# display.net
KiCad netlist of a schematic drawn in EAGLE
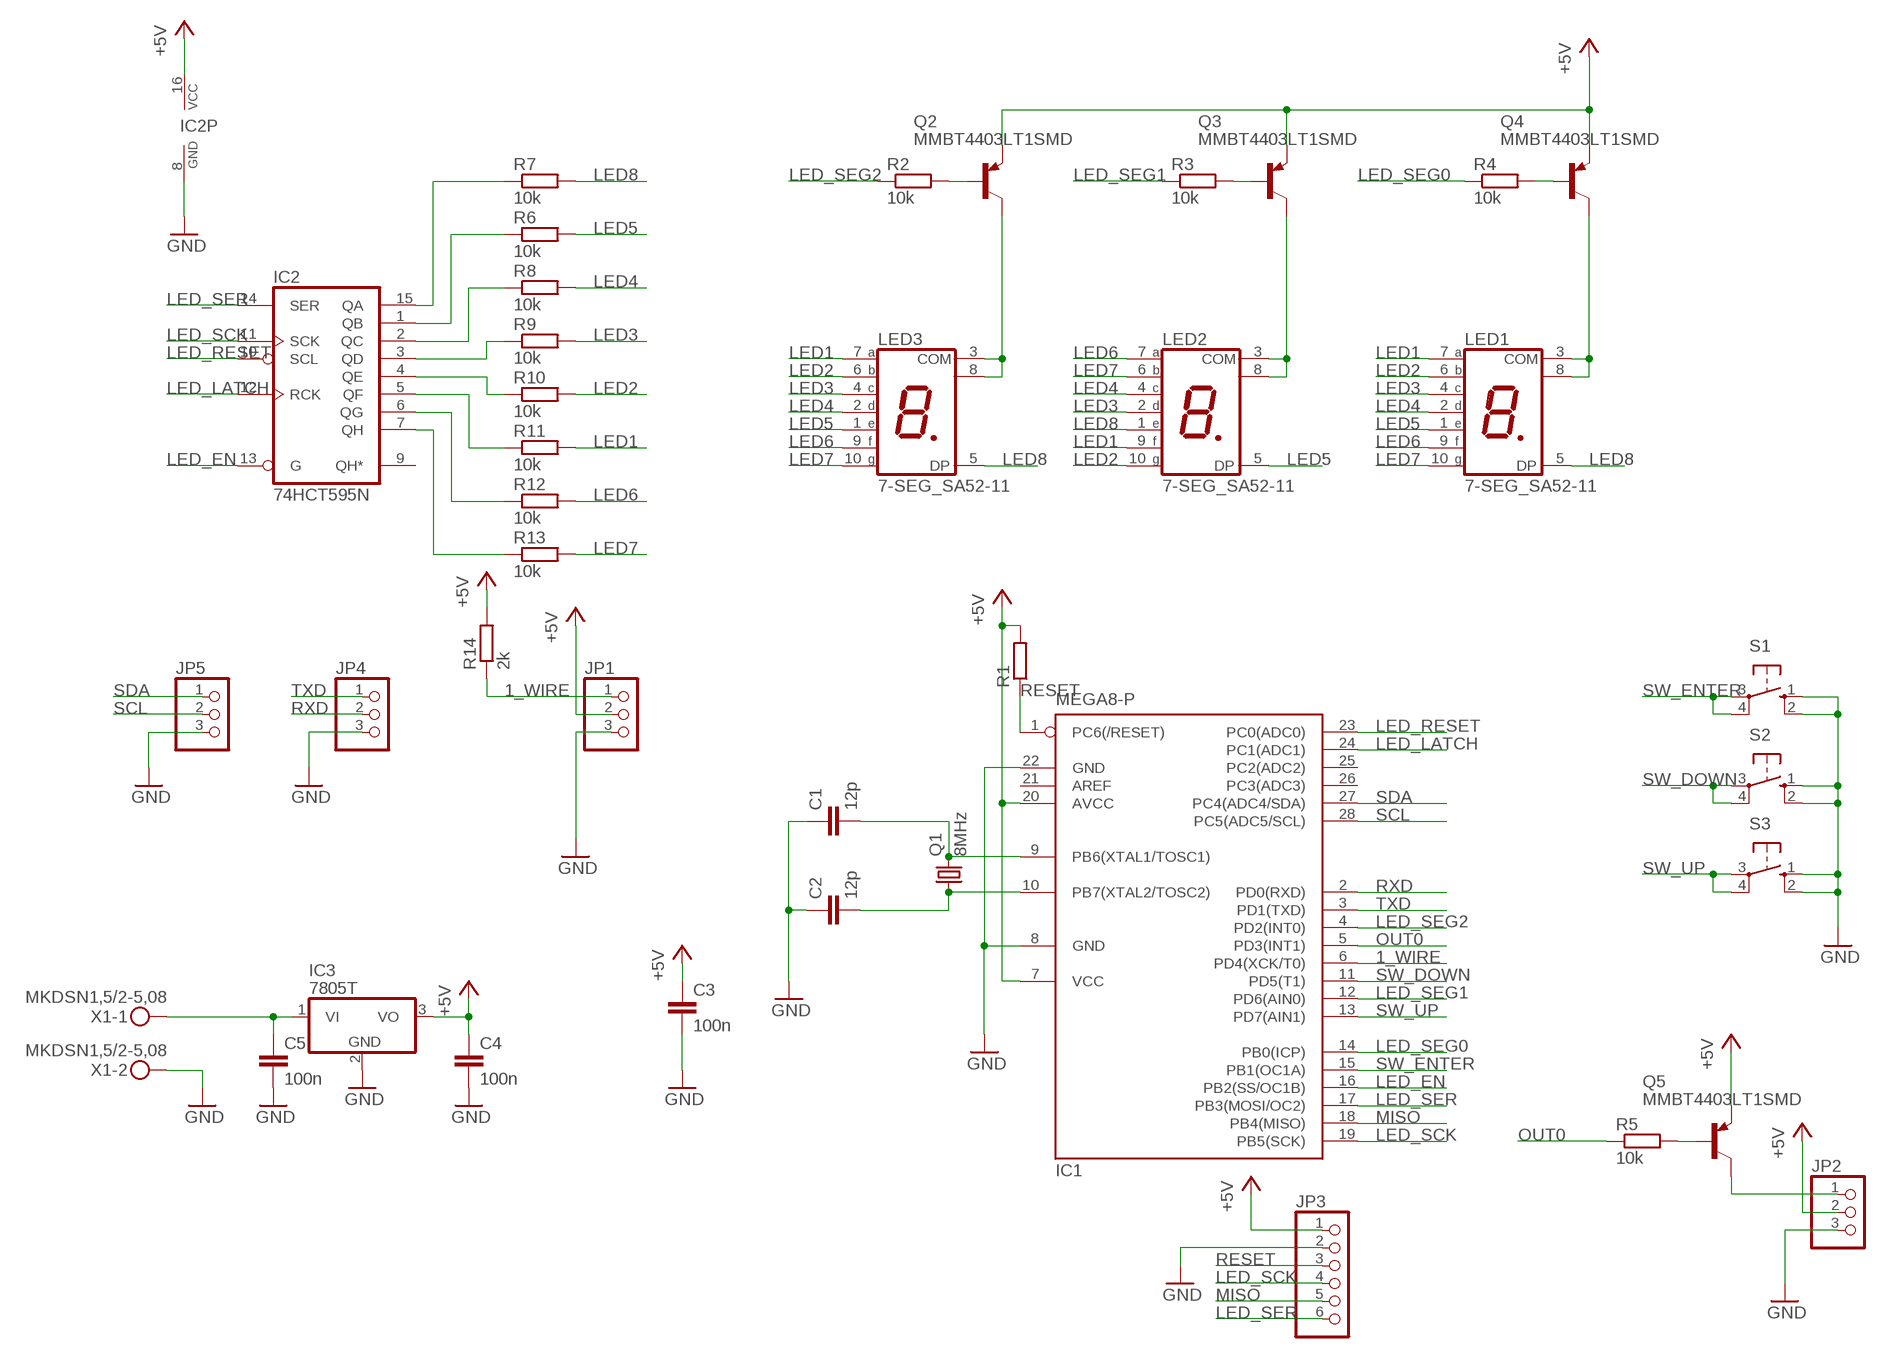
[diagram p0: schematic, sheet 1]

(export (version "E")
  (design (tool "Eeschema 10.0.6"))
  (components
    (comp (ref "C1")
      (value "12p")
      (footprint "eagle-import:C050-035X075")
      (libsource (lib "eagle-import") (part "C-EU050-035X075"))
    )
    (comp (ref "C2")
      (value "12p")
      (footprint "eagle-import:C050-035X075")
      (libsource (lib "eagle-import") (part "C-EU050-035X075"))
    )
    (comp (ref "C3")
      (value "100n")
      (footprint "eagle-import:C050-030X075")
      (libsource (lib "eagle-import") (part "C-EU050-030X075"))
    )
    (comp (ref "C4")
      (value "100n")
      (footprint "eagle-import:C050-030X075")
      (libsource (lib "eagle-import") (part "C-EU050-030X075"))
    )
    (comp (ref "C5")
      (value "100n")
      (footprint "eagle-import:C050-030X075")
      (libsource (lib "eagle-import") (part "C-EU050-030X075"))
    )
    (comp (ref "IC1")
      (value "MEGA8-P")
      (footprint "eagle-import:DIL28-3")
      (libsource (lib "eagle-import") (part "MEGA8-P"))
    )
    (comp (ref "IC2")
      (value "74HCT595N")
      (footprint "eagle-import:DIL16")
      (libsource (lib "eagle-import") (part "74595NHCT"))
    )
    (comp (ref "IC3")
      (value "7805T")
      (footprint "eagle-import:TO220H")
      (libsource (lib "eagle-import") (part "78T05"))
    )
    (comp (ref "JP1")
      (value "PINHD-1X3")
      (footprint "eagle-import:1X03")
      (libsource (lib "eagle-import") (part "PINHD-1X3"))
    )
    (comp (ref "JP2")
      (value "PINHD-1X3")
      (footprint "eagle-import:1X03")
      (libsource (lib "eagle-import") (part "PINHD-1X3"))
    )
    (comp (ref "JP3")
      (value "PINHD-1X6")
      (footprint "eagle-import:1X06")
      (libsource (lib "eagle-import") (part "PINHD-1X6"))
    )
    (comp (ref "JP4")
      (value "PINHD-1X3")
      (footprint "eagle-import:1X03")
      (libsource (lib "eagle-import") (part "PINHD-1X3"))
    )
    (comp (ref "JP5")
      (value "PINHD-1X3")
      (footprint "eagle-import:1X03")
      (libsource (lib "eagle-import") (part "PINHD-1X3"))
    )
    (comp (ref "LED1")
      (value "7-SEG_SA52-11")
      (footprint "eagle-import:SA52-11")
      (libsource (lib "eagle-import") (part "7-SEG_SA52-11"))
    )
    (comp (ref "LED2")
      (value "7-SEG_SA52-11")
      (footprint "eagle-import:SA52-11")
      (libsource (lib "eagle-import") (part "7-SEG_SA52-11"))
    )
    (comp (ref "LED3")
      (value "7-SEG_SA52-11")
      (footprint "eagle-import:SA52-11")
      (libsource (lib "eagle-import") (part "7-SEG_SA52-11"))
    )
    (comp (ref "Q1")
      (value "8MHz")
      (footprint "eagle-import:HC49U70")
      (libsource (lib "eagle-import") (part "CRYSTALHC49U70"))
    )
    (comp (ref "Q2")
      (value "MMBT4403LT1SMD")
      (footprint "eagle-import:SOT23-BEC")
      (libsource (lib "eagle-import") (part "MMBT4403SMDLT1"))
    )
    (comp (ref "Q3")
      (value "MMBT4403LT1SMD")
      (footprint "eagle-import:SOT23-BEC")
      (libsource (lib "eagle-import") (part "MMBT4403SMDLT1"))
    )
    (comp (ref "Q4")
      (value "MMBT4403LT1SMD")
      (footprint "eagle-import:SOT23-BEC")
      (libsource (lib "eagle-import") (part "MMBT4403SMDLT1"))
    )
    (comp (ref "Q5")
      (value "MMBT4403LT1SMD")
      (footprint "eagle-import:SOT23-BEC")
      (libsource (lib "eagle-import") (part "MMBT4403SMDLT1"))
    )
    (comp (ref "R1")
      (value "R-EU_R1206")
      (footprint "eagle-import:R1206")
      (libsource (lib "eagle-import") (part "R-EU_R1206"))
    )
    (comp (ref "R2")
      (value "10k")
      (footprint "eagle-import:M1206")
      (libsource (lib "eagle-import") (part "R-EU_M1206"))
    )
    (comp (ref "R3")
      (value "10k")
      (footprint "eagle-import:M1206")
      (libsource (lib "eagle-import") (part "R-EU_M1206"))
    )
    (comp (ref "R4")
      (value "10k")
      (footprint "eagle-import:M1206")
      (libsource (lib "eagle-import") (part "R-EU_M1206"))
    )
    (comp (ref "R5")
      (value "10k")
      (footprint "eagle-import:M1206")
      (libsource (lib "eagle-import") (part "R-EU_M1206"))
    )
    (comp (ref "R6")
      (value "10k")
      (footprint "eagle-import:M1206")
      (libsource (lib "eagle-import") (part "R-EU_M1206"))
    )
    (comp (ref "R7")
      (value "10k")
      (footprint "eagle-import:M1206")
      (libsource (lib "eagle-import") (part "R-EU_M1206"))
    )
    (comp (ref "R8")
      (value "10k")
      (footprint "eagle-import:M1206")
      (libsource (lib "eagle-import") (part "R-EU_M1206"))
    )
    (comp (ref "R9")
      (value "10k")
      (footprint "eagle-import:M1206")
      (libsource (lib "eagle-import") (part "R-EU_M1206"))
    )
    (comp (ref "R10")
      (value "10k")
      (footprint "eagle-import:M1206")
      (libsource (lib "eagle-import") (part "R-EU_M1206"))
    )
    (comp (ref "R11")
      (value "10k")
      (footprint "eagle-import:M1206")
      (libsource (lib "eagle-import") (part "R-EU_M1206"))
    )
    (comp (ref "R12")
      (value "10k")
      (footprint "eagle-import:M1206")
      (libsource (lib "eagle-import") (part "R-EU_M1206"))
    )
    (comp (ref "R13")
      (value "10k")
      (footprint "eagle-import:M1206")
      (libsource (lib "eagle-import") (part "R-EU_M1206"))
    )
    (comp (ref "R14")
      (value "2k")
      (footprint "eagle-import:M1206")
      (libsource (lib "eagle-import") (part "R-EU_M1206"))
    )
    (comp (ref "S1")
      (value "10-XX")
      (footprint "eagle-import:B3F-10XX")
      (fields (field (name "MPN") "B3F-1000"))
      (libsource (lib "eagle-import") (part "10-XX"))
    )
    (comp (ref "S2")
      (value "10-XX")
      (footprint "eagle-import:B3F-10XX")
      (fields (field (name "MPN") "B3F-1000"))
      (libsource (lib "eagle-import") (part "10-XX"))
    )
    (comp (ref "S3")
      (value "10-XX")
      (footprint "eagle-import:B3F-10XX")
      (fields (field (name "MPN") "B3F-1000"))
      (libsource (lib "eagle-import") (part "10-XX"))
    )
    (comp (ref "X1")
      (value "MKDSN1,5/2-5,08")
      (footprint "eagle-import:MKDSN1,5_2-5,08")
      (fields (field (name "MPN") "MKDSN 1,5/2-5.08"))
      (libsource (lib "eagle-import") (part "MKDSN1,5/2-5,08"))
    )
  )
  (nets
    (net (code "1") (name "+5V") (class "Default")
      (node (ref "C3") (pin "1") (pinfunction "1_1") (pintype "passive"))
      (node (ref "C4") (pin "1") (pinfunction "1_1") (pintype "passive"))
      (node (ref "IC1") (pin "20") (pinfunction "AVCC_20") (pintype "power_in"))
      (node (ref "IC1") (pin "7") (pinfunction "VCC_7") (pintype "power_in"))
      (node (ref "IC2") (pin "16") (pinfunction "VCC_16") (pintype "power_in"))
      (node (ref "IC3") (pin "3") (pinfunction "VO_3") (pintype "passive"))
      (node (ref "JP1") (pin "2") (pinfunction "2_2") (pintype "passive"))
      (node (ref "JP2") (pin "2") (pinfunction "2_2") (pintype "passive"))
      (node (ref "JP3") (pin "1") (pinfunction "1_1") (pintype "passive"))
      (node (ref "Q2") (pin "E") (pinfunction "E_E") (pintype "passive"))
      (node (ref "Q3") (pin "E") (pinfunction "E_E") (pintype "passive"))
      (node (ref "Q4") (pin "E") (pinfunction "E_E") (pintype "passive"))
      (node (ref "Q5") (pin "E") (pinfunction "E_E") (pintype "passive"))
      (node (ref "R1") (pin "2") (pinfunction "2_2") (pintype "passive"))
      (node (ref "R14") (pin "2") (pinfunction "2_2") (pintype "passive"))
    )
    (net (code "2") (name "/1_WIRE") (class "Default")
      (node (ref "IC1") (pin "6") (pinfunction "PD4(XCK/T0)_6") (pintype "bidirectional"))
      (node (ref "JP1") (pin "1") (pinfunction "1_1") (pintype "passive"))
      (node (ref "R14") (pin "1") (pinfunction "1_1") (pintype "passive"))
    )
    (net (code "3") (name "/LED1") (class "Default")
      (node (ref "LED1") (pin "7") (pinfunction "A_7") (pintype "passive"))
      (node (ref "LED2") (pin "9") (pinfunction "F_9") (pintype "passive"))
      (node (ref "LED3") (pin "7") (pinfunction "A_7") (pintype "passive"))
      (node (ref "R11") (pin "2") (pinfunction "2_2") (pintype "passive"))
    )
    (net (code "4") (name "/LED2") (class "Default")
      (node (ref "LED1") (pin "6") (pinfunction "B_6") (pintype "passive"))
      (node (ref "LED2") (pin "10") (pinfunction "G_10") (pintype "passive"))
      (node (ref "LED3") (pin "6") (pinfunction "B_6") (pintype "passive"))
      (node (ref "R10") (pin "2") (pinfunction "2_2") (pintype "passive"))
    )
    (net (code "5") (name "/LED3") (class "Default")
      (node (ref "LED1") (pin "4") (pinfunction "C_4") (pintype "passive"))
      (node (ref "LED2") (pin "2") (pinfunction "D_2") (pintype "passive"))
      (node (ref "LED3") (pin "4") (pinfunction "C_4") (pintype "passive"))
      (node (ref "R9") (pin "2") (pinfunction "2_2") (pintype "passive"))
    )
    (net (code "6") (name "/LED4") (class "Default")
      (node (ref "LED1") (pin "2") (pinfunction "D_2") (pintype "passive"))
      (node (ref "LED2") (pin "4") (pinfunction "C_4") (pintype "passive"))
      (node (ref "LED3") (pin "2") (pinfunction "D_2") (pintype "passive"))
      (node (ref "R8") (pin "2") (pinfunction "2_2") (pintype "passive"))
    )
    (net (code "7") (name "/LED5") (class "Default")
      (node (ref "LED1") (pin "1") (pinfunction "E_1") (pintype "passive"))
      (node (ref "LED2") (pin "5") (pinfunction "DP_5") (pintype "passive"))
      (node (ref "LED3") (pin "1") (pinfunction "E_1") (pintype "passive"))
      (node (ref "R6") (pin "2") (pinfunction "2_2") (pintype "passive"))
    )
    (net (code "8") (name "/LED6") (class "Default")
      (node (ref "LED1") (pin "9") (pinfunction "F_9") (pintype "passive"))
      (node (ref "LED2") (pin "7") (pinfunction "A_7") (pintype "passive"))
      (node (ref "LED3") (pin "9") (pinfunction "F_9") (pintype "passive"))
      (node (ref "R12") (pin "2") (pinfunction "2_2") (pintype "passive"))
    )
    (net (code "9") (name "/LED7") (class "Default")
      (node (ref "LED1") (pin "10") (pinfunction "G_10") (pintype "passive"))
      (node (ref "LED2") (pin "6") (pinfunction "B_6") (pintype "passive"))
      (node (ref "LED3") (pin "10") (pinfunction "G_10") (pintype "passive"))
      (node (ref "R13") (pin "2") (pinfunction "2_2") (pintype "passive"))
    )
    (net (code "10") (name "/LED8") (class "Default")
      (node (ref "LED1") (pin "5") (pinfunction "DP_5") (pintype "passive"))
      (node (ref "LED2") (pin "1") (pinfunction "E_1") (pintype "passive"))
      (node (ref "LED3") (pin "5") (pinfunction "DP_5") (pintype "passive"))
      (node (ref "R7") (pin "2") (pinfunction "2_2") (pintype "passive"))
    )
    (net (code "11") (name "/LED_EN") (class "Default")
      (node (ref "IC1") (pin "16") (pinfunction "PB2(SS/OC1B)_16") (pintype "bidirectional"))
      (node (ref "IC2") (pin "13") (pinfunction "G_13") (pintype "input"))
    )
    (net (code "12") (name "/LED_LATCH") (class "Default")
      (node (ref "IC1") (pin "24") (pinfunction "PC1(ADC1)_24") (pintype "bidirectional"))
      (node (ref "IC2") (pin "12") (pinfunction "RCK_12") (pintype "input"))
    )
    (net (code "13") (name "/LED_RESET") (class "Default")
      (node (ref "IC1") (pin "23") (pinfunction "PC0(ADC0)_23") (pintype "bidirectional"))
      (node (ref "IC2") (pin "10") (pinfunction "SCL_10") (pintype "input"))
    )
    (net (code "14") (name "/LED_SCK") (class "Default")
      (node (ref "IC1") (pin "19") (pinfunction "PB5(SCK)_19") (pintype "bidirectional"))
      (node (ref "IC2") (pin "11") (pinfunction "SCK_11") (pintype "input"))
      (node (ref "JP3") (pin "4") (pinfunction "4_4") (pintype "passive"))
    )
    (net (code "15") (name "/LED_SEG0") (class "Default")
      (node (ref "IC1") (pin "14") (pinfunction "PB0(ICP)_14") (pintype "bidirectional"))
      (node (ref "R4") (pin "1") (pinfunction "1_1") (pintype "passive"))
    )
    (net (code "16") (name "/LED_SEG1") (class "Default")
      (node (ref "IC1") (pin "12") (pinfunction "PD6(AIN0)_12") (pintype "bidirectional"))
      (node (ref "R3") (pin "1") (pinfunction "1_1") (pintype "passive"))
    )
    (net (code "17") (name "/LED_SEG2") (class "Default")
      (node (ref "IC1") (pin "4") (pinfunction "PD2(INT0)_4") (pintype "bidirectional"))
      (node (ref "R2") (pin "1") (pinfunction "1_1") (pintype "passive"))
    )
    (net (code "18") (name "/LED_SER") (class "Default")
      (node (ref "IC1") (pin "17") (pinfunction "PB3(MOSI/OC2)_17") (pintype "bidirectional"))
      (node (ref "IC2") (pin "14") (pinfunction "SER_14") (pintype "input"))
      (node (ref "JP3") (pin "6") (pinfunction "6_6") (pintype "passive"))
    )
    (net (code "19") (name "/MISO") (class "Default")
      (node (ref "IC1") (pin "18") (pinfunction "PB4(MISO)_18") (pintype "bidirectional"))
      (node (ref "JP3") (pin "5") (pinfunction "5_5") (pintype "passive"))
    )
    (net (code "20") (name "/OUT0") (class "Default")
      (node (ref "IC1") (pin "5") (pinfunction "PD3(INT1)_5") (pintype "bidirectional"))
      (node (ref "R5") (pin "1") (pinfunction "1_1") (pintype "passive"))
    )
    (net (code "21") (name "/RESET") (class "Default")
      (node (ref "IC1") (pin "1") (pinfunction "PC6(/RESET)_1") (pintype "bidirectional"))
      (node (ref "JP3") (pin "3") (pinfunction "3_3") (pintype "passive"))
      (node (ref "R1") (pin "1") (pinfunction "1_1") (pintype "passive"))
    )
    (net (code "22") (name "/RXD") (class "Default")
      (node (ref "IC1") (pin "2") (pinfunction "PD0(RXD)_2") (pintype "bidirectional"))
      (node (ref "JP4") (pin "2") (pinfunction "2_2") (pintype "passive"))
    )
    (net (code "23") (name "/SCL") (class "Default")
      (node (ref "IC1") (pin "28") (pinfunction "PC5(ADC5/SCL)_28") (pintype "bidirectional"))
      (node (ref "JP5") (pin "2") (pinfunction "2_2") (pintype "passive"))
    )
    (net (code "24") (name "/SDA") (class "Default")
      (node (ref "IC1") (pin "27") (pinfunction "PC4(ADC4/SDA)_27") (pintype "bidirectional"))
      (node (ref "JP5") (pin "1") (pinfunction "1_1") (pintype "passive"))
    )
    (net (code "25") (name "/SW_DOWN") (class "Default")
      (node (ref "IC1") (pin "11") (pinfunction "PD5(T1)_11") (pintype "bidirectional"))
      (node (ref "S2") (pin "3") (pinfunction "P_3") (pintype "passive"))
      (node (ref "S2") (pin "4") (pinfunction "P1_4") (pintype "passive"))
    )
    (net (code "26") (name "/SW_ENTER") (class "Default")
      (node (ref "IC1") (pin "15") (pinfunction "PB1(OC1A)_15") (pintype "bidirectional"))
      (node (ref "S1") (pin "3") (pinfunction "P_3") (pintype "passive"))
      (node (ref "S1") (pin "4") (pinfunction "P1_4") (pintype "passive"))
    )
    (net (code "27") (name "/SW_UP") (class "Default")
      (node (ref "IC1") (pin "13") (pinfunction "PD7(AIN1)_13") (pintype "bidirectional"))
      (node (ref "S3") (pin "3") (pinfunction "P_3") (pintype "passive"))
      (node (ref "S3") (pin "4") (pinfunction "P1_4") (pintype "passive"))
    )
    (net (code "28") (name "/TXD") (class "Default")
      (node (ref "IC1") (pin "3") (pinfunction "PD1(TXD)_3") (pintype "bidirectional"))
      (node (ref "JP4") (pin "1") (pinfunction "1_1") (pintype "passive"))
    )
    (net (code "29") (name "GND") (class "Default")
      (node (ref "C1") (pin "1") (pinfunction "1_1") (pintype "passive"))
      (node (ref "C2") (pin "1") (pinfunction "1_1") (pintype "passive"))
      (node (ref "C3") (pin "2") (pinfunction "2_2") (pintype "passive"))
      (node (ref "C4") (pin "2") (pinfunction "2_2") (pintype "passive"))
      (node (ref "C5") (pin "2") (pinfunction "2_2") (pintype "passive"))
      (node (ref "IC1") (pin "22") (pinfunction "GND_22") (pintype "power_in"))
      (node (ref "IC1") (pin "8") (pinfunction "GND_8") (pintype "power_in"))
      (node (ref "IC2") (pin "8") (pinfunction "GND_8") (pintype "power_in"))
      (node (ref "IC3") (pin "2") (pinfunction "GND_2") (pintype "passive"))
      (node (ref "JP1") (pin "3") (pinfunction "3_3") (pintype "passive"))
      (node (ref "JP2") (pin "3") (pinfunction "3_3") (pintype "passive"))
      (node (ref "JP3") (pin "2") (pinfunction "2_2") (pintype "passive"))
      (node (ref "JP4") (pin "3") (pinfunction "3_3") (pintype "passive"))
      (node (ref "JP5") (pin "3") (pinfunction "3_3") (pintype "passive"))
      (node (ref "S1") (pin "1") (pinfunction "S_1") (pintype "passive"))
      (node (ref "S1") (pin "2") (pinfunction "S1_2") (pintype "passive"))
      (node (ref "S2") (pin "1") (pinfunction "S_1") (pintype "passive"))
      (node (ref "S2") (pin "2") (pinfunction "S1_2") (pintype "passive"))
      (node (ref "S3") (pin "1") (pinfunction "S_1") (pintype "passive"))
      (node (ref "S3") (pin "2") (pinfunction "S1_2") (pintype "passive"))
      (node (ref "X1") (pin "2") (pinfunction "KL_2") (pintype "passive"))
    )
    (net (code "30") (name "Net-(IC1-PB6(XTAL1{slash}TOSC1))") (class "Default")
      (node (ref "C1") (pin "2") (pinfunction "2_2") (pintype "passive"))
      (node (ref "IC1") (pin "9") (pinfunction "PB6(XTAL1/TOSC1)_9") (pintype "bidirectional"))
      (node (ref "Q1") (pin "2") (pinfunction "2_2") (pintype "passive"))
    )
    (net (code "31") (name "Net-(IC1-PB7(XTAL2{slash}TOSC2))") (class "Default")
      (node (ref "C2") (pin "2") (pinfunction "2_2") (pintype "passive"))
      (node (ref "IC1") (pin "10") (pinfunction "PB7(XTAL2/TOSC2)_10") (pintype "bidirectional"))
      (node (ref "Q1") (pin "1") (pinfunction "1_1") (pintype "passive"))
    )
    (net (code "32") (name "Net-(IC2A-QA)") (class "Default")
      (node (ref "IC2") (pin "15") (pinfunction "QA_15") (pintype "tri_state"))
      (node (ref "R7") (pin "1") (pinfunction "1_1") (pintype "passive"))
    )
    (net (code "33") (name "Net-(IC2A-QB)") (class "Default")
      (node (ref "IC2") (pin "1") (pinfunction "QB_1") (pintype "tri_state"))
      (node (ref "R6") (pin "1") (pinfunction "1_1") (pintype "passive"))
    )
    (net (code "34") (name "Net-(IC2A-QC)") (class "Default")
      (node (ref "IC2") (pin "2") (pinfunction "QC_2") (pintype "tri_state"))
      (node (ref "R8") (pin "1") (pinfunction "1_1") (pintype "passive"))
    )
    (net (code "35") (name "Net-(IC2A-QD)") (class "Default")
      (node (ref "IC2") (pin "3") (pinfunction "QD_3") (pintype "tri_state"))
      (node (ref "R9") (pin "1") (pinfunction "1_1") (pintype "passive"))
    )
    (net (code "36") (name "Net-(IC2A-QE)") (class "Default")
      (node (ref "IC2") (pin "4") (pinfunction "QE_4") (pintype "tri_state"))
      (node (ref "R10") (pin "1") (pinfunction "1_1") (pintype "passive"))
    )
    (net (code "37") (name "Net-(IC2A-QF)") (class "Default")
      (node (ref "IC2") (pin "5") (pinfunction "QF_5") (pintype "tri_state"))
      (node (ref "R11") (pin "1") (pinfunction "1_1") (pintype "passive"))
    )
    (net (code "38") (name "Net-(IC2A-QG)") (class "Default")
      (node (ref "IC2") (pin "6") (pinfunction "QG_6") (pintype "tri_state"))
      (node (ref "R12") (pin "1") (pinfunction "1_1") (pintype "passive"))
    )
    (net (code "39") (name "Net-(IC2A-QH)") (class "Default")
      (node (ref "IC2") (pin "7") (pinfunction "QH_7") (pintype "tri_state"))
      (node (ref "R13") (pin "1") (pinfunction "1_1") (pintype "passive"))
    )
    (net (code "40") (name "Net-(IC3-VI)") (class "Default")
      (node (ref "C5") (pin "1") (pinfunction "1_1") (pintype "passive"))
      (node (ref "IC3") (pin "1") (pinfunction "VI_1") (pintype "input"))
      (node (ref "X1") (pin "1") (pinfunction "KL_1") (pintype "passive"))
    )
    (net (code "41") (name "Net-(JP2-Pad1)") (class "Default")
      (node (ref "JP2") (pin "1") (pinfunction "1_1") (pintype "passive"))
      (node (ref "Q5") (pin "C") (pinfunction "C_C") (pintype "passive"))
    )
    (net (code "42") (name "Net-(LED1-COM-Pad3)") (class "Default")
      (node (ref "LED1") (pin "3") (pinfunction "COM_3") (pintype "passive"))
      (node (ref "LED1") (pin "8") (pinfunction "COM_8") (pintype "passive"))
      (node (ref "Q4") (pin "C") (pinfunction "C_C") (pintype "passive"))
    )
    (net (code "43") (name "Net-(LED2-COM-Pad3)") (class "Default")
      (node (ref "LED2") (pin "3") (pinfunction "COM_3") (pintype "passive"))
      (node (ref "LED2") (pin "8") (pinfunction "COM_8") (pintype "passive"))
      (node (ref "Q3") (pin "C") (pinfunction "C_C") (pintype "passive"))
    )
    (net (code "44") (name "Net-(LED3-COM-Pad3)") (class "Default")
      (node (ref "LED3") (pin "3") (pinfunction "COM_3") (pintype "passive"))
      (node (ref "LED3") (pin "8") (pinfunction "COM_8") (pintype "passive"))
      (node (ref "Q2") (pin "C") (pinfunction "C_C") (pintype "passive"))
    )
    (net (code "45") (name "Net-(Q2-PadB)") (class "Default")
      (node (ref "Q2") (pin "B") (pinfunction "B_B") (pintype "passive"))
      (node (ref "R2") (pin "2") (pinfunction "2_2") (pintype "passive"))
    )
    (net (code "46") (name "Net-(Q3-PadB)") (class "Default")
      (node (ref "Q3") (pin "B") (pinfunction "B_B") (pintype "passive"))
      (node (ref "R3") (pin "2") (pinfunction "2_2") (pintype "passive"))
    )
    (net (code "47") (name "Net-(Q4-PadB)") (class "Default")
      (node (ref "Q4") (pin "B") (pinfunction "B_B") (pintype "passive"))
      (node (ref "R4") (pin "2") (pinfunction "2_2") (pintype "passive"))
    )
    (net (code "48") (name "Net-(Q5-PadB)") (class "Default")
      (node (ref "Q5") (pin "B") (pinfunction "B_B") (pintype "passive"))
      (node (ref "R5") (pin "2") (pinfunction "2_2") (pintype "passive"))
    )
    (net (code "49") (name "unconnected-(IC1-AREF-Pad21)") (class "Default")
      (node (ref "IC1") (pin "21") (pinfunction "AREF_21") (pintype "passive"))
    )
    (net (code "50") (name "unconnected-(IC1-PC2(ADC2)-Pad25)") (class "Default")
      (node (ref "IC1") (pin "25") (pinfunction "PC2(ADC2)_25") (pintype "bidirectional"))
    )
    (net (code "51") (name "unconnected-(IC1-PC3(ADC3)-Pad26)") (class "Default")
      (node (ref "IC1") (pin "26") (pinfunction "PC3(ADC3)_26") (pintype "bidirectional"))
    )
    (net (code "52") (name "unconnected-(IC2A-QH*-Pad9)") (class "Default")
      (node (ref "IC2") (pin "9") (pinfunction "QH*_9") (pintype "tri_state"))
    )
  )
)
